# ADS1299.net
KiCad netlist of a schematic drawn in Altium Designer
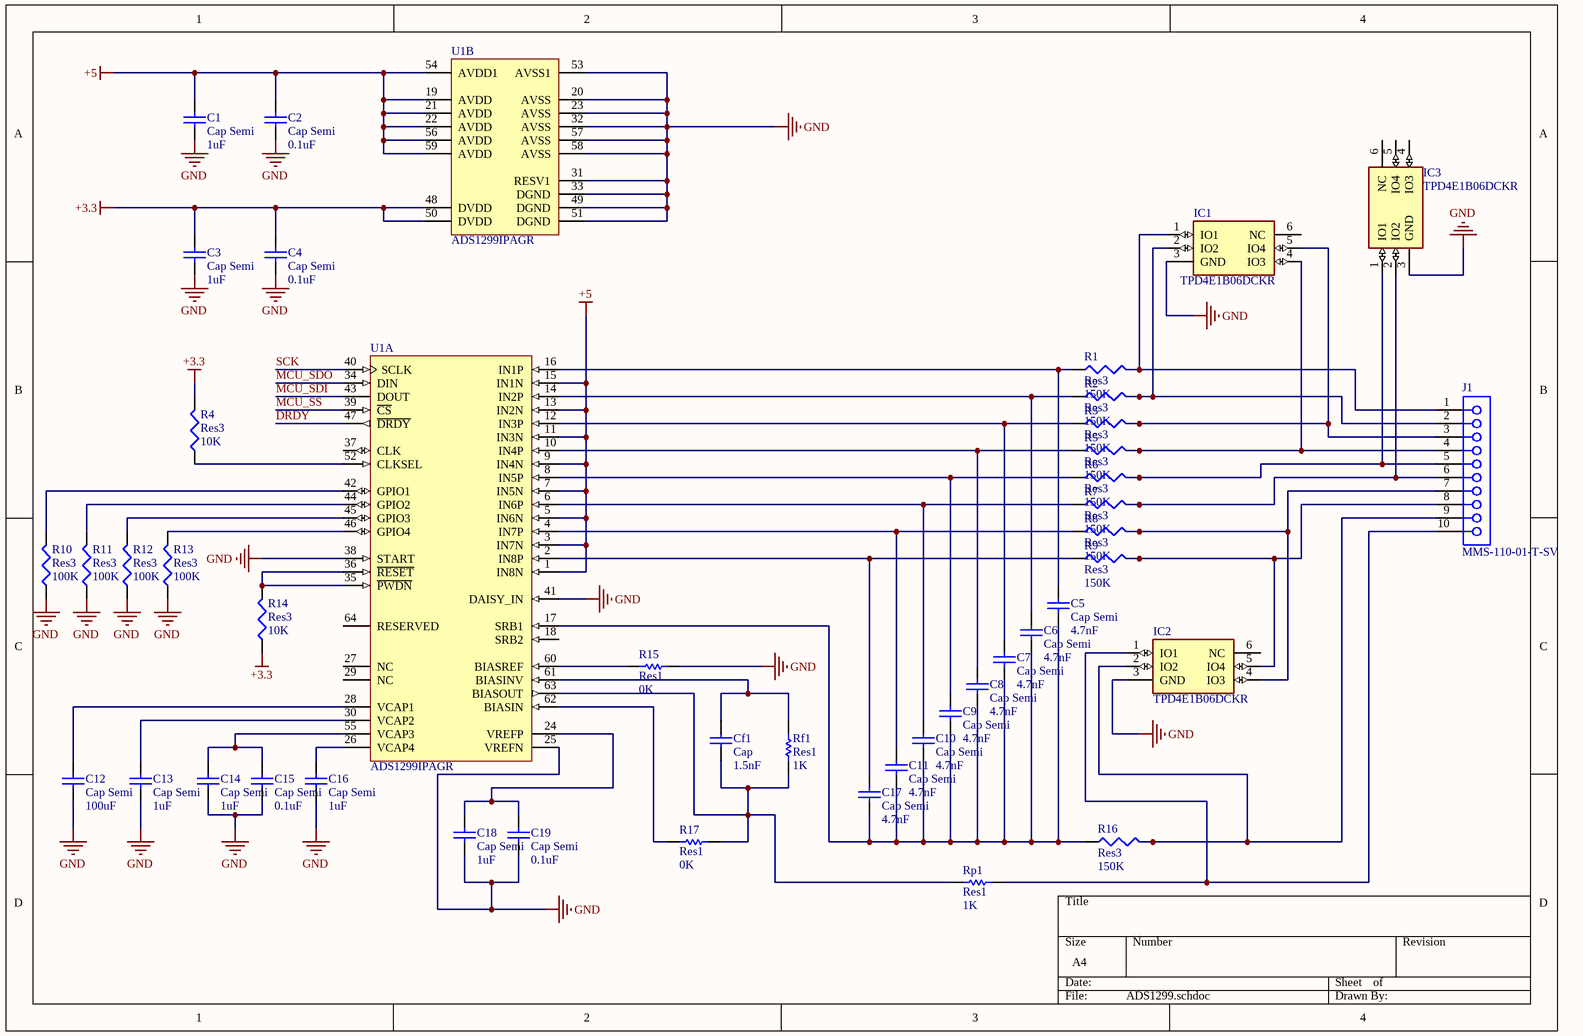
[diagram p0: ADS1299.schdoc]

(export (version "E")
  (design (tool "Eeschema 10.0.6"))
  (components
    (comp (ref "C1")
      (value "Cap Semi")
      (footprint "0805c")
      (description "Capacitor (Semiconductor SIM Model)")
      (fields (field (name "ALTIUM_VALUE") "1uF") (field (name "PUBLISHER") "Altium Limited"))
      (libsource (lib "Miscellaneous Devices") (part "Cap Semi"))
    )
    (comp (ref "C2")
      (value "Cap Semi")
      (footprint "0805c")
      (description "Capacitor (Semiconductor SIM Model)")
      (fields (field (name "ALTIUM_VALUE") "0.1uF") (field (name "PUBLISHER") "Altium Limited"))
      (libsource (lib "Miscellaneous Devices") (part "Cap Semi"))
    )
    (comp (ref "C3")
      (value "Cap Semi")
      (footprint "0805c")
      (description "Capacitor (Semiconductor SIM Model)")
      (fields (field (name "ALTIUM_VALUE") "1uF") (field (name "PUBLISHER") "Altium Limited"))
      (libsource (lib "Miscellaneous Devices") (part "Cap Semi"))
    )
    (comp (ref "C4")
      (value "Cap Semi")
      (footprint "0805c")
      (description "Capacitor (Semiconductor SIM Model)")
      (fields (field (name "ALTIUM_VALUE") "0.1uF") (field (name "PUBLISHER") "Altium Limited"))
      (libsource (lib "Miscellaneous Devices") (part "Cap Semi"))
    )
    (comp (ref "C5")
      (value "Cap Semi")
      (footprint "0805c")
      (description "Capacitor (Semiconductor SIM Model)")
      (fields (field (name "ALTIUM_VALUE") "4.7nF") (field (name "PUBLISHER") "Altium Limited"))
      (libsource (lib "Miscellaneous Devices") (part "Cap Semi"))
    )
    (comp (ref "C6")
      (value "Cap Semi")
      (footprint "0805c")
      (description "Capacitor (Semiconductor SIM Model)")
      (fields (field (name "ALTIUM_VALUE") "4.7nF") (field (name "PUBLISHER") "Altium Limited"))
      (libsource (lib "Miscellaneous Devices") (part "Cap Semi"))
    )
    (comp (ref "C7")
      (value "Cap Semi")
      (footprint "0805c")
      (description "Capacitor (Semiconductor SIM Model)")
      (fields (field (name "ALTIUM_VALUE") "4.7nF") (field (name "PUBLISHER") "Altium Limited"))
      (libsource (lib "Miscellaneous Devices") (part "Cap Semi"))
    )
    (comp (ref "C8")
      (value "Cap Semi")
      (footprint "0805c")
      (description "Capacitor (Semiconductor SIM Model)")
      (fields (field (name "ALTIUM_VALUE") "4.7nF") (field (name "PUBLISHER") "Altium Limited"))
      (libsource (lib "Miscellaneous Devices") (part "Cap Semi"))
    )
    (comp (ref "C9")
      (value "Cap Semi")
      (footprint "0805c")
      (description "Capacitor (Semiconductor SIM Model)")
      (fields (field (name "ALTIUM_VALUE") "4.7nF") (field (name "PUBLISHER") "Altium Limited"))
      (libsource (lib "Miscellaneous Devices") (part "Cap Semi"))
    )
    (comp (ref "C10")
      (value "Cap Semi")
      (footprint "0805c")
      (description "Capacitor (Semiconductor SIM Model)")
      (fields (field (name "ALTIUM_VALUE") "4.7nF") (field (name "PUBLISHER") "Altium Limited"))
      (libsource (lib "Miscellaneous Devices") (part "Cap Semi"))
    )
    (comp (ref "C11")
      (value "Cap Semi")
      (footprint "0805c")
      (description "Capacitor (Semiconductor SIM Model)")
      (fields (field (name "ALTIUM_VALUE") "4.7nF") (field (name "PUBLISHER") "Altium Limited"))
      (libsource (lib "Miscellaneous Devices") (part "Cap Semi"))
    )
    (comp (ref "C12")
      (value "Cap Semi")
      (footprint "0805c")
      (description "Capacitor (Semiconductor SIM Model)")
      (fields (field (name "ALTIUM_VALUE") "100uF") (field (name "PUBLISHER") "Altium Limited"))
      (libsource (lib "Miscellaneous Devices") (part "Cap Semi"))
    )
    (comp (ref "C13")
      (value "Cap Semi")
      (footprint "0805c")
      (description "Capacitor (Semiconductor SIM Model)")
      (fields (field (name "ALTIUM_VALUE") "1uF") (field (name "PUBLISHER") "Altium Limited"))
      (libsource (lib "Miscellaneous Devices") (part "Cap Semi"))
    )
    (comp (ref "C14")
      (value "Cap Semi")
      (footprint "0805c")
      (description "Capacitor (Semiconductor SIM Model)")
      (fields (field (name "ALTIUM_VALUE") "1uF") (field (name "PUBLISHER") "Altium Limited"))
      (libsource (lib "Miscellaneous Devices") (part "Cap Semi"))
    )
    (comp (ref "C15")
      (value "Cap Semi")
      (footprint "0805c")
      (description "Capacitor (Semiconductor SIM Model)")
      (fields (field (name "ALTIUM_VALUE") "0.1uF") (field (name "PUBLISHER") "Altium Limited"))
      (libsource (lib "Miscellaneous Devices") (part "Cap Semi"))
    )
    (comp (ref "C16")
      (value "Cap Semi")
      (footprint "0805c")
      (description "Capacitor (Semiconductor SIM Model)")
      (fields (field (name "ALTIUM_VALUE") "1uF") (field (name "PUBLISHER") "Altium Limited"))
      (libsource (lib "Miscellaneous Devices") (part "Cap Semi"))
    )
    (comp (ref "C17")
      (value "Cap Semi")
      (footprint "0805c")
      (description "Capacitor (Semiconductor SIM Model)")
      (fields (field (name "ALTIUM_VALUE") "4.7nF") (field (name "PUBLISHER") "Altium Limited"))
      (libsource (lib "Miscellaneous Devices") (part "Cap Semi"))
    )
    (comp (ref "C18")
      (value "Cap Semi")
      (footprint "0805c")
      (description "Capacitor (Semiconductor SIM Model)")
      (fields (field (name "ALTIUM_VALUE") "1uF") (field (name "PUBLISHER") "Altium Limited"))
      (libsource (lib "Miscellaneous Devices") (part "Cap Semi"))
    )
    (comp (ref "C19")
      (value "Cap Semi")
      (footprint "0805c")
      (description "Capacitor (Semiconductor SIM Model)")
      (fields (field (name "ALTIUM_VALUE") "0.1uF") (field (name "PUBLISHER") "Altium Limited"))
      (libsource (lib "Miscellaneous Devices") (part "Cap Semi"))
    )
    (comp (ref "Cf1")
      (value "Cap")
      (footprint "102")
      (description "Capacitor")
      (fields (field (name "ALTIUM_VALUE") "1.5nF") (field (name "PUBLISHER") "Altium Limited"))
      (libsource (lib "Miscellaneous Devices") (part "Cap"))
    )
    (comp (ref "IC1")
      (value "TPD4E1B06DCKR")
      (footprint "SOT363")
      (description "Integrated Circuit")
      (fields
        (field (name "MOUSER PART NUMBER") "595-TPD4E1B06DCKR")
        (field (name "RS PART NUMBER") "8255330P")
      )
      (libsource (lib "") (part "TPD4E1B06DCKR_1"))
    )
    (comp (ref "IC2")
      (value "TPD4E1B06DCKR")
      (footprint "SOT363")
      (description "Integrated Circuit")
      (fields
        (field (name "MOUSER PART NUMBER") "595-TPD4E1B06DCKR")
        (field (name "RS PART NUMBER") "8255330P")
      )
      (libsource (lib "") (part "TPD4E1B06DCKR_1"))
    )
    (comp (ref "IC3")
      (value "TPD4E1B06DCKR")
      (footprint "SOT363")
      (description "Integrated Circuit")
      (fields
        (field (name "MOUSER PART NUMBER") "595-TPD4E1B06DCKR")
        (field (name "RS PART NUMBER") "8255330P")
      )
      (libsource (lib "*") (part "TPD4E1B06DCKR"))
    )
    (comp (ref "J1")
      (value "MMS-110-01-T-SV")
      (footprint "HDR1X10")
      (fields (field (name "MANUFACTURER") "Samtec"))
      (libsource (lib "Altium Content Vault") (part "SMTC-MMS-110-01-X-SV"))
    )
    (comp (ref "R1")
      (value "Res3")
      (footprint "0805")
      (description "Resistor")
      (fields (field (name "ALTIUM_VALUE") "150K") (field (name "PUBLISHER") "Altium Limited"))
      (libsource (lib "Miscellaneous Devices") (part "Res3"))
    )
    (comp (ref "R2")
      (value "Res3")
      (footprint "0805")
      (description "Resistor")
      (fields (field (name "ALTIUM_VALUE") "150K") (field (name "PUBLISHER") "Altium Limited"))
      (libsource (lib "Miscellaneous Devices") (part "Res3"))
    )
    (comp (ref "R3")
      (value "Res3")
      (footprint "0805")
      (description "Resistor")
      (fields (field (name "ALTIUM_VALUE") "150K") (field (name "PUBLISHER") "Altium Limited"))
      (libsource (lib "Miscellaneous Devices") (part "Res3"))
    )
    (comp (ref "R4")
      (value "Res3")
      (footprint "0805")
      (description "Resistor")
      (fields (field (name "ALTIUM_VALUE") "10K") (field (name "PUBLISHER") "Altium Limited"))
      (libsource (lib "Miscellaneous Devices") (part "Res3"))
    )
    (comp (ref "R5")
      (value "Res3")
      (footprint "0805")
      (description "Resistor")
      (fields (field (name "ALTIUM_VALUE") "150K") (field (name "PUBLISHER") "Altium Limited"))
      (libsource (lib "Miscellaneous Devices") (part "Res3"))
    )
    (comp (ref "R6")
      (value "Res3")
      (footprint "0805")
      (description "Resistor")
      (fields (field (name "ALTIUM_VALUE") "150K") (field (name "PUBLISHER") "Altium Limited"))
      (libsource (lib "Miscellaneous Devices") (part "Res3"))
    )
    (comp (ref "R7")
      (value "Res3")
      (footprint "0805")
      (description "Resistor")
      (fields (field (name "ALTIUM_VALUE") "150K") (field (name "PUBLISHER") "Altium Limited"))
      (libsource (lib "Miscellaneous Devices") (part "Res3"))
    )
    (comp (ref "R8")
      (value "Res3")
      (footprint "0805")
      (description "Resistor")
      (fields (field (name "ALTIUM_VALUE") "150K") (field (name "PUBLISHER") "Altium Limited"))
      (libsource (lib "Miscellaneous Devices") (part "Res3"))
    )
    (comp (ref "R9")
      (value "Res3")
      (footprint "0805")
      (description "Resistor")
      (fields (field (name "ALTIUM_VALUE") "150K") (field (name "PUBLISHER") "Altium Limited"))
      (libsource (lib "Miscellaneous Devices") (part "Res3"))
    )
    (comp (ref "R10")
      (value "Res3")
      (footprint "0805")
      (description "Resistor")
      (fields (field (name "ALTIUM_VALUE") "100K") (field (name "PUBLISHER") "Altium Limited"))
      (libsource (lib "Miscellaneous Devices") (part "Res3"))
    )
    (comp (ref "R11")
      (value "Res3")
      (footprint "0805")
      (description "Resistor")
      (fields (field (name "ALTIUM_VALUE") "100K") (field (name "PUBLISHER") "Altium Limited"))
      (libsource (lib "Miscellaneous Devices") (part "Res3"))
    )
    (comp (ref "R12")
      (value "Res3")
      (footprint "0805")
      (description "Resistor")
      (fields (field (name "ALTIUM_VALUE") "100K") (field (name "PUBLISHER") "Altium Limited"))
      (libsource (lib "Miscellaneous Devices") (part "Res3"))
    )
    (comp (ref "R13")
      (value "Res3")
      (footprint "0805")
      (description "Resistor")
      (fields (field (name "ALTIUM_VALUE") "100K") (field (name "PUBLISHER") "Altium Limited"))
      (libsource (lib "Miscellaneous Devices") (part "Res3"))
    )
    (comp (ref "R14")
      (value "Res3")
      (footprint "0805")
      (description "Resistor")
      (fields (field (name "ALTIUM_VALUE") "10K") (field (name "PUBLISHER") "Altium Limited"))
      (libsource (lib "Miscellaneous Devices") (part "Res3"))
    )
    (comp (ref "R15")
      (value "Res1")
      (footprint "RB0.4    &9")
      (description "Resistor")
      (fields (field (name "ALTIUM_VALUE") "0K") (field (name "PUBLISHER") "Altium Limited"))
      (libsource (lib "Miscellaneous Devices") (part "Res1"))
    )
    (comp (ref "R16")
      (value "Res3")
      (footprint "0805")
      (description "Resistor")
      (fields (field (name "ALTIUM_VALUE") "150K") (field (name "PUBLISHER") "Altium Limited"))
      (libsource (lib "Miscellaneous Devices") (part "Res3"))
    )
    (comp (ref "R17")
      (value "Res1")
      (footprint "RB0.4    &9")
      (description "Resistor")
      (fields (field (name "ALTIUM_VALUE") "0K") (field (name "PUBLISHER") "Altium Limited"))
      (libsource (lib "Miscellaneous Devices") (part "Res1"))
    )
    (comp (ref "Rf1")
      (value "Res1")
      (footprint "RB0.4    &9")
      (description "Resistor")
      (fields (field (name "ALTIUM_VALUE") "1K") (field (name "PUBLISHER") "Altium Limited"))
      (libsource (lib "Miscellaneous Devices") (part "Res1"))
    )
    (comp (ref "Rp1")
      (value "Res1")
      (footprint "RB0.4    &9")
      (description "Resistor")
      (fields (field (name "ALTIUM_VALUE") "1K") (field (name "PUBLISHER") "Altium Limited"))
      (libsource (lib "Miscellaneous Devices") (part "Res1"))
    )
    (comp (ref "U1")
      (value "ADS1299IPAGR")
      (footprint "PAG0064A_M")
      (fields (field (name "MANUFACTURER") "Texas Instruments"))
      (libsource (lib "Altium Content Vault") (part "TI-ADS1299-PAG-64"))
    )
  )
  (nets
    (net (code "1") (name "+3.3") (class "Default")
      (node (ref "C3") (pin "2") (pinfunction "2_2") (pintype "passive"))
      (node (ref "C4") (pin "2") (pinfunction "2_2") (pintype "passive"))
      (node (ref "R14") (pin "1") (pinfunction "1_1") (pintype "passive"))
      (node (ref "R4") (pin "2") (pinfunction "2_2") (pintype "passive"))
      (node (ref "U1") (pin "48") (pinfunction "DVDD_48") (pintype "power_in"))
      (node (ref "U1") (pin "50") (pinfunction "DVDD_50") (pintype "power_in"))
    )
    (net (code "2") (name "+5") (class "Default")
      (node (ref "C1") (pin "2") (pinfunction "2_2") (pintype "passive"))
      (node (ref "C2") (pin "2") (pinfunction "2_2") (pintype "passive"))
      (node (ref "U1") (pin "1") (pinfunction "IN8N_1") (pintype "input"))
      (node (ref "U1") (pin "11") (pinfunction "IN3N_11") (pintype "input"))
      (node (ref "U1") (pin "13") (pinfunction "IN2N_13") (pintype "input"))
      (node (ref "U1") (pin "15") (pinfunction "IN1N_15") (pintype "input"))
      (node (ref "U1") (pin "19") (pinfunction "AVDD_19") (pintype "power_in"))
      (node (ref "U1") (pin "21") (pinfunction "AVDD_21") (pintype "power_in"))
      (node (ref "U1") (pin "22") (pinfunction "AVDD_22") (pintype "power_in"))
      (node (ref "U1") (pin "3") (pinfunction "IN7N_3") (pintype "input"))
      (node (ref "U1") (pin "5") (pinfunction "IN6N_5") (pintype "input"))
      (node (ref "U1") (pin "54") (pinfunction "AVDD1_54") (pintype "power_in"))
      (node (ref "U1") (pin "56") (pinfunction "AVDD_56") (pintype "power_in"))
      (node (ref "U1") (pin "59") (pinfunction "AVDD_59") (pintype "power_in"))
      (node (ref "U1") (pin "7") (pinfunction "IN5N_7") (pintype "input"))
      (node (ref "U1") (pin "9") (pinfunction "IN4N_9") (pintype "input"))
    )
    (net (code "3") (name "/DRDY") (class "Default")
      (node (ref "U1") (pin "47") (pinfunction "~{DRDY}_47") (pintype "output"))
    )
    (net (code "4") (name "/MCU_SDI") (class "Default")
      (node (ref "U1") (pin "43") (pinfunction "DOUT_43") (pintype "tri_state"))
    )
    (net (code "5") (name "/MCU_SDO") (class "Default")
      (node (ref "U1") (pin "34") (pinfunction "DIN_34") (pintype "input"))
    )
    (net (code "6") (name "/MCU_SS") (class "Default")
      (node (ref "U1") (pin "39") (pinfunction "~{CS}_39") (pintype "input"))
    )
    (net (code "7") (name "/SCK") (class "Default")
      (node (ref "U1") (pin "40") (pinfunction "SCLK_40") (pintype "input"))
    )
    (net (code "8") (name "GND") (class "Default")
      (node (ref "C1") (pin "1") (pinfunction "1_1") (pintype "passive"))
      (node (ref "C12") (pin "1") (pinfunction "1_1") (pintype "passive"))
      (node (ref "C13") (pin "1") (pinfunction "1_1") (pintype "passive"))
      (node (ref "C14") (pin "1") (pinfunction "1_1") (pintype "passive"))
      (node (ref "C15") (pin "1") (pinfunction "1_1") (pintype "passive"))
      (node (ref "C16") (pin "1") (pinfunction "1_1") (pintype "passive"))
      (node (ref "C18") (pin "1") (pinfunction "1_1") (pintype "passive"))
      (node (ref "C19") (pin "1") (pinfunction "1_1") (pintype "passive"))
      (node (ref "C2") (pin "1") (pinfunction "1_1") (pintype "passive"))
      (node (ref "C3") (pin "1") (pinfunction "1_1") (pintype "passive"))
      (node (ref "C4") (pin "1") (pinfunction "1_1") (pintype "passive"))
      (node (ref "IC1") (pin "3") (pinfunction "GND_3") (pintype "power_in"))
      (node (ref "IC2") (pin "3") (pinfunction "GND_3") (pintype "power_in"))
      (node (ref "IC3") (pin "3") (pinfunction "GND_3") (pintype "power_in"))
      (node (ref "R10") (pin "1") (pinfunction "1_1") (pintype "passive"))
      (node (ref "R11") (pin "1") (pinfunction "1_1") (pintype "passive"))
      (node (ref "R12") (pin "1") (pinfunction "1_1") (pintype "passive"))
      (node (ref "R13") (pin "1") (pinfunction "1_1") (pintype "passive"))
      (node (ref "R15") (pin "1") (pinfunction "1_1") (pintype "passive"))
      (node (ref "U1") (pin "20") (pinfunction "AVSS_20") (pintype "power_in"))
      (node (ref "U1") (pin "23") (pinfunction "AVSS_23") (pintype "power_in"))
      (node (ref "U1") (pin "25") (pinfunction "VREFN_25") (pintype "passive"))
      (node (ref "U1") (pin "31") (pinfunction "RESV1_31") (pintype "power_in"))
      (node (ref "U1") (pin "32") (pinfunction "AVSS_32") (pintype "power_in"))
      (node (ref "U1") (pin "33") (pinfunction "DGND_33") (pintype "power_in"))
      (node (ref "U1") (pin "38") (pinfunction "START_38") (pintype "input"))
      (node (ref "U1") (pin "41") (pinfunction "DAISY_IN_41") (pintype "input"))
      (node (ref "U1") (pin "49") (pinfunction "DGND_49") (pintype "power_in"))
      (node (ref "U1") (pin "51") (pinfunction "DGND_51") (pintype "power_in"))
      (node (ref "U1") (pin "53") (pinfunction "AVSS1_53") (pintype "power_in"))
      (node (ref "U1") (pin "57") (pinfunction "AVSS_57") (pintype "power_in"))
      (node (ref "U1") (pin "58") (pinfunction "AVSS_58") (pintype "power_in"))
    )
    (net (code "9") (name "Net-(IC1-IO1)") (class "Default")
      (node (ref "IC1") (pin "1") (pinfunction "IO1_1") (pintype "bidirectional"))
      (node (ref "J1") (pin "1") (pinfunction "1_1") (pintype "passive"))
      (node (ref "R1") (pin "2") (pinfunction "2_2") (pintype "passive"))
    )
    (net (code "10") (name "Net-(IC1-IO2)") (class "Default")
      (node (ref "IC1") (pin "2") (pinfunction "IO2_2") (pintype "bidirectional"))
      (node (ref "J1") (pin "2") (pinfunction "2_2") (pintype "passive"))
      (node (ref "R2") (pin "2") (pinfunction "2_2") (pintype "passive"))
    )
    (net (code "11") (name "Net-(IC1-IO3)") (class "Default")
      (node (ref "IC1") (pin "4") (pinfunction "IO3_4") (pintype "bidirectional"))
      (node (ref "J1") (pin "4") (pinfunction "4_4") (pintype "passive"))
      (node (ref "R5") (pin "2") (pinfunction "2_2") (pintype "passive"))
    )
    (net (code "12") (name "Net-(IC1-IO4)") (class "Default")
      (node (ref "IC1") (pin "5") (pinfunction "IO4_5") (pintype "bidirectional"))
      (node (ref "J1") (pin "3") (pinfunction "3_3") (pintype "passive"))
      (node (ref "R3") (pin "2") (pinfunction "2_2") (pintype "passive"))
    )
    (net (code "13") (name "Net-(IC2-IO1)") (class "Default")
      (node (ref "IC2") (pin "1") (pinfunction "IO1_1") (pintype "bidirectional"))
      (node (ref "J1") (pin "10") (pinfunction "10_10") (pintype "passive"))
      (node (ref "Rp1") (pin "2") (pinfunction "2_2") (pintype "passive"))
    )
    (net (code "14") (name "Net-(IC2-IO2)") (class "Default")
      (node (ref "IC2") (pin "2") (pinfunction "IO2_2") (pintype "bidirectional"))
      (node (ref "J1") (pin "9") (pinfunction "9_9") (pintype "passive"))
      (node (ref "R16") (pin "2") (pinfunction "2_2") (pintype "passive"))
    )
    (net (code "15") (name "Net-(IC2-IO3)") (class "Default")
      (node (ref "IC2") (pin "4") (pinfunction "IO3_4") (pintype "bidirectional"))
      (node (ref "J1") (pin "7") (pinfunction "7_7") (pintype "passive"))
      (node (ref "R8") (pin "2") (pinfunction "2_2") (pintype "passive"))
    )
    (net (code "16") (name "Net-(IC2-IO4)") (class "Default")
      (node (ref "IC2") (pin "5") (pinfunction "IO4_5") (pintype "bidirectional"))
      (node (ref "J1") (pin "8") (pinfunction "8_8") (pintype "passive"))
      (node (ref "R9") (pin "2") (pinfunction "2_2") (pintype "passive"))
    )
    (net (code "17") (name "Net-(IC3-IO1)") (class "Default")
      (node (ref "IC3") (pin "1") (pinfunction "IO1_1") (pintype "bidirectional"))
      (node (ref "J1") (pin "5") (pinfunction "5_5") (pintype "passive"))
      (node (ref "R6") (pin "2") (pinfunction "2_2") (pintype "passive"))
    )
    (net (code "18") (name "Net-(IC3-IO2)") (class "Default")
      (node (ref "IC3") (pin "2") (pinfunction "IO2_2") (pintype "bidirectional"))
      (node (ref "J1") (pin "6") (pinfunction "6_6") (pintype "passive"))
      (node (ref "R7") (pin "2") (pinfunction "2_2") (pintype "passive"))
    )
    (net (code "19") (name "Net-(U1A-BIASIN)") (class "Default")
      (node (ref "R17") (pin "1") (pinfunction "1_1") (pintype "passive"))
      (node (ref "U1") (pin "62") (pinfunction "BIASIN_62") (pintype "input"))
    )
    (net (code "20") (name "Net-(U1A-BIASINV)") (class "Default")
      (node (ref "Cf1") (pin "2") (pinfunction "2_2") (pintype "passive"))
      (node (ref "Rf1") (pin "2") (pinfunction "2_2") (pintype "passive"))
      (node (ref "U1") (pin "61") (pinfunction "BIASINV_61") (pintype "input"))
    )
    (net (code "21") (name "Net-(U1A-BIASOUT)") (class "Default")
      (node (ref "Cf1") (pin "1") (pinfunction "1_1") (pintype "passive"))
      (node (ref "R17") (pin "2") (pinfunction "2_2") (pintype "passive"))
      (node (ref "Rf1") (pin "1") (pinfunction "1_1") (pintype "passive"))
      (node (ref "Rp1") (pin "1") (pinfunction "1_1") (pintype "passive"))
      (node (ref "U1") (pin "63") (pinfunction "BIASOUT_63") (pintype "output"))
    )
    (net (code "22") (name "Net-(U1A-BIASREF)") (class "Default")
      (node (ref "R15") (pin "2") (pinfunction "2_2") (pintype "passive"))
      (node (ref "U1") (pin "60") (pinfunction "BIASREF_60") (pintype "input"))
    )
    (net (code "23") (name "Net-(U1A-CLKSEL)") (class "Default")
      (node (ref "R4") (pin "1") (pinfunction "1_1") (pintype "passive"))
      (node (ref "U1") (pin "52") (pinfunction "CLKSEL_52") (pintype "input"))
    )
    (net (code "24") (name "Net-(U1A-GPIO1)") (class "Default")
      (node (ref "R10") (pin "2") (pinfunction "2_2") (pintype "passive"))
      (node (ref "U1") (pin "42") (pinfunction "GPIO1_42") (pintype "bidirectional"))
    )
    (net (code "25") (name "Net-(U1A-GPIO2)") (class "Default")
      (node (ref "R11") (pin "2") (pinfunction "2_2") (pintype "passive"))
      (node (ref "U1") (pin "44") (pinfunction "GPIO2_44") (pintype "bidirectional"))
    )
    (net (code "26") (name "Net-(U1A-GPIO3)") (class "Default")
      (node (ref "R12") (pin "2") (pinfunction "2_2") (pintype "passive"))
      (node (ref "U1") (pin "45") (pinfunction "GPIO3_45") (pintype "bidirectional"))
    )
    (net (code "27") (name "Net-(U1A-GPIO4)") (class "Default")
      (node (ref "R13") (pin "2") (pinfunction "2_2") (pintype "passive"))
      (node (ref "U1") (pin "46") (pinfunction "GPIO4_46") (pintype "bidirectional"))
    )
    (net (code "28") (name "Net-(U1A-IN1P)") (class "Default")
      (node (ref "C5") (pin "2") (pinfunction "2_2") (pintype "passive"))
      (node (ref "R1") (pin "1") (pinfunction "1_1") (pintype "passive"))
      (node (ref "U1") (pin "16") (pinfunction "IN1P_16") (pintype "input"))
    )
    (net (code "29") (name "Net-(U1A-IN2P)") (class "Default")
      (node (ref "C6") (pin "2") (pinfunction "2_2") (pintype "passive"))
      (node (ref "R2") (pin "1") (pinfunction "1_1") (pintype "passive"))
      (node (ref "U1") (pin "14") (pinfunction "IN2P_14") (pintype "input"))
    )
    (net (code "30") (name "Net-(U1A-IN3P)") (class "Default")
      (node (ref "C7") (pin "2") (pinfunction "2_2") (pintype "passive"))
      (node (ref "R3") (pin "1") (pinfunction "1_1") (pintype "passive"))
      (node (ref "U1") (pin "12") (pinfunction "IN3P_12") (pintype "input"))
    )
    (net (code "31") (name "Net-(U1A-IN4P)") (class "Default")
      (node (ref "C8") (pin "2") (pinfunction "2_2") (pintype "passive"))
      (node (ref "R5") (pin "1") (pinfunction "1_1") (pintype "passive"))
      (node (ref "U1") (pin "10") (pinfunction "IN4P_10") (pintype "input"))
    )
    (net (code "32") (name "Net-(U1A-IN5P)") (class "Default")
      (node (ref "C9") (pin "2") (pinfunction "2_2") (pintype "passive"))
      (node (ref "R6") (pin "1") (pinfunction "1_1") (pintype "passive"))
      (node (ref "U1") (pin "8") (pinfunction "IN5P_8") (pintype "input"))
    )
    (net (code "33") (name "Net-(U1A-IN6P)") (class "Default")
      (node (ref "C10") (pin "2") (pinfunction "2_2") (pintype "passive"))
      (node (ref "R7") (pin "1") (pinfunction "1_1") (pintype "passive"))
      (node (ref "U1") (pin "6") (pinfunction "IN6P_6") (pintype "input"))
    )
    (net (code "34") (name "Net-(U1A-IN7P)") (class "Default")
      (node (ref "C11") (pin "2") (pinfunction "2_2") (pintype "passive"))
      (node (ref "R8") (pin "1") (pinfunction "1_1") (pintype "passive"))
      (node (ref "U1") (pin "4") (pinfunction "IN7P_4") (pintype "input"))
    )
    (net (code "35") (name "Net-(U1A-IN8P)") (class "Default")
      (node (ref "C17") (pin "2") (pinfunction "2_2") (pintype "passive"))
      (node (ref "R9") (pin "1") (pinfunction "1_1") (pintype "passive"))
      (node (ref "U1") (pin "2") (pinfunction "IN8P_2") (pintype "input"))
    )
    (net (code "36") (name "Net-(U1A-SRB1)") (class "Default")
      (node (ref "C10") (pin "1") (pinfunction "1_1") (pintype "passive"))
      (node (ref "C11") (pin "1") (pinfunction "1_1") (pintype "passive"))
      (node (ref "C17") (pin "1") (pinfunction "1_1") (pintype "passive"))
      (node (ref "C5") (pin "1") (pinfunction "1_1") (pintype "passive"))
      (node (ref "C6") (pin "1") (pinfunction "1_1") (pintype "passive"))
      (node (ref "C7") (pin "1") (pinfunction "1_1") (pintype "passive"))
      (node (ref "C8") (pin "1") (pinfunction "1_1") (pintype "passive"))
      (node (ref "C9") (pin "1") (pinfunction "1_1") (pintype "passive"))
      (node (ref "R16") (pin "1") (pinfunction "1_1") (pintype "passive"))
      (node (ref "U1") (pin "17") (pinfunction "SRB1_17") (pintype "input"))
    )
    (net (code "37") (name "Net-(U1A-VCAP1)") (class "Default")
      (node (ref "C12") (pin "2") (pinfunction "2_2") (pintype "passive"))
      (node (ref "U1") (pin "28") (pinfunction "VCAP1_28") (pintype "passive"))
    )
    (net (code "38") (name "Net-(U1A-VCAP2)") (class "Default")
      (node (ref "C13") (pin "2") (pinfunction "2_2") (pintype "passive"))
      (node (ref "U1") (pin "30") (pinfunction "VCAP2_30") (pintype "passive"))
    )
    (net (code "39") (name "Net-(U1A-VCAP3)") (class "Default")
      (node (ref "C14") (pin "2") (pinfunction "2_2") (pintype "passive"))
      (node (ref "C15") (pin "2") (pinfunction "2_2") (pintype "passive"))
      (node (ref "U1") (pin "55") (pinfunction "VCAP3_55") (pintype "passive"))
    )
    (net (code "40") (name "Net-(U1A-VCAP4)") (class "Default")
      (node (ref "C16") (pin "2") (pinfunction "2_2") (pintype "passive"))
      (node (ref "U1") (pin "26") (pinfunction "VCAP4_26") (pintype "passive"))
    )
    (net (code "41") (name "Net-(U1A-VREFP)") (class "Default")
      (node (ref "C18") (pin "2") (pinfunction "2_2") (pintype "passive"))
      (node (ref "C19") (pin "2") (pinfunction "2_2") (pintype "passive"))
      (node (ref "U1") (pin "24") (pinfunction "VREFP_24") (pintype "passive"))
    )
    (net (code "42") (name "Net-(U1A-~{PWDN})") (class "Default")
      (node (ref "R14") (pin "2") (pinfunction "2_2") (pintype "passive"))
      (node (ref "U1") (pin "35") (pinfunction "~{PWDN}_35") (pintype "input"))
      (node (ref "U1") (pin "36") (pinfunction "~{RESET}_36") (pintype "input"))
    )
    (net (code "43") (name "unconnected-(IC1-NC-Pad6)") (class "Default")
      (node (ref "IC1") (pin "6") (pinfunction "NC_6") (pintype "passive"))
    )
    (net (code "44") (name "unconnected-(IC2-NC-Pad6)") (class "Default")
      (node (ref "IC2") (pin "6") (pinfunction "NC_6") (pintype "passive"))
    )
    (net (code "45") (name "unconnected-(IC3-IO3-Pad4)") (class "Default")
      (node (ref "IC3") (pin "4") (pinfunction "IO3_4") (pintype "bidirectional"))
    )
    (net (code "46") (name "unconnected-(IC3-IO4-Pad5)") (class "Default")
      (node (ref "IC3") (pin "5") (pinfunction "IO4_5") (pintype "bidirectional"))
    )
    (net (code "47") (name "unconnected-(IC3-NC-Pad6)") (class "Default")
      (node (ref "IC3") (pin "6") (pinfunction "NC_6") (pintype "passive"))
    )
    (net (code "48") (name "unconnected-(U1A-CLK-Pad37)") (class "Default")
      (node (ref "U1") (pin "37") (pinfunction "CLK_37") (pintype "bidirectional"))
    )
    (net (code "49") (name "unconnected-(U1A-NC-Pad27)") (class "Default")
      (node (ref "U1") (pin "27") (pinfunction "NC_27") (pintype "passive"))
    )
    (net (code "50") (name "unconnected-(U1A-NC-Pad29)") (class "Default")
      (node (ref "U1") (pin "29") (pinfunction "NC_29") (pintype "passive"))
    )
    (net (code "51") (name "unconnected-(U1A-RESERVED-Pad64)") (class "Default")
      (node (ref "U1") (pin "64") (pinfunction "RESERVED_64") (pintype "passive"))
    )
    (net (code "52") (name "unconnected-(U1A-SRB2-Pad18)") (class "Default")
      (node (ref "U1") (pin "18") (pinfunction "SRB2_18") (pintype "input"))
    )
  )
)
